# fabfm.net
KiCad netlist of a schematic drawn in EAGLE
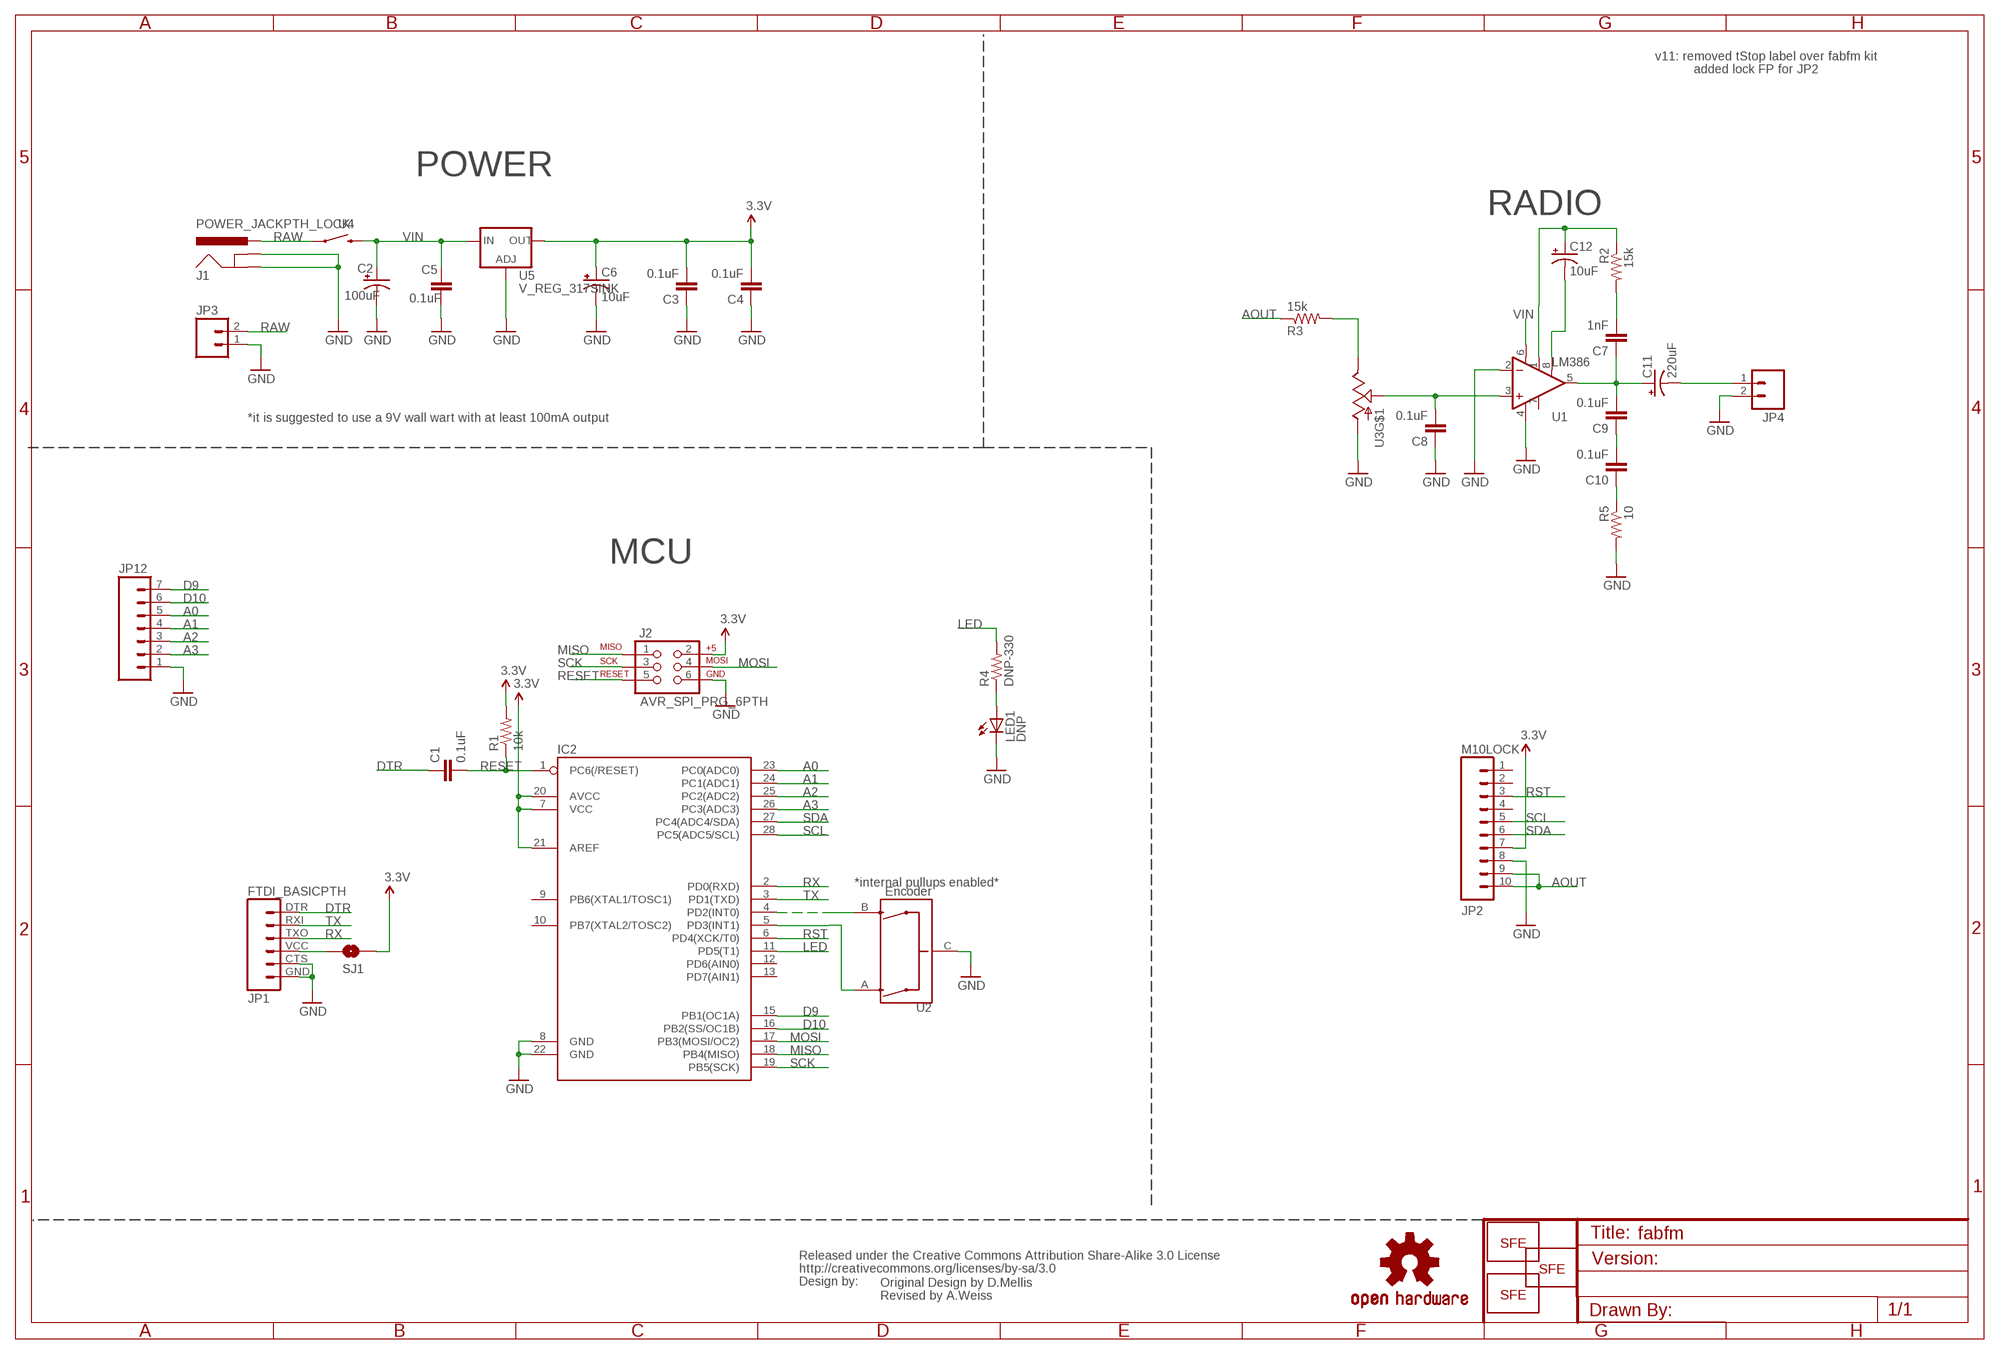
[diagram p0: schematic, sheet 1]

(export (version "E")
  (design (tool "Eeschema 10.0.6"))
  (components
    (comp (ref "C1")
      (value "0.1uF")
      (footprint "eagle-import:CAP-PTH-SMALL-KIT")
      (libsource (lib "eagle-import") (part "CAPKIT"))
    )
    (comp (ref "C2")
      (value "100uF")
      (footprint "eagle-import:CPOL-RADIAL-100UF-25V")
      (libsource (lib "eagle-import") (part "CAP_POLPTH1"))
    )
    (comp (ref "C3")
      (value "0.1uF")
      (footprint "eagle-import:CAP-PTH-SMALL-KIT")
      (libsource (lib "eagle-import") (part "CAPKIT"))
    )
    (comp (ref "C4")
      (value "0.1uF")
      (footprint "eagle-import:CAP-PTH-SMALL-KIT")
      (libsource (lib "eagle-import") (part "CAPKIT"))
    )
    (comp (ref "C5")
      (value "0.1uF")
      (footprint "eagle-import:CAP-PTH-SMALL-KIT")
      (libsource (lib "eagle-import") (part "CAPKIT"))
    )
    (comp (ref "C6")
      (value "10uF")
      (footprint "eagle-import:CPOL-RADIAL-10UF-25V")
      (libsource (lib "eagle-import") (part "CAP_POLPTH2"))
    )
    (comp (ref "C7")
      (value "1nF")
      (footprint "eagle-import:CAP-PTH-SMALL-KIT")
      (libsource (lib "eagle-import") (part "CAPKIT"))
    )
    (comp (ref "C8")
      (value "0.1uF")
      (footprint "eagle-import:CAP-PTH-SMALL-KIT")
      (libsource (lib "eagle-import") (part "CAPKIT"))
    )
    (comp (ref "C9")
      (value "0.1uF")
      (footprint "eagle-import:CAP-PTH-SMALL-KIT")
      (libsource (lib "eagle-import") (part "CAPKIT"))
    )
    (comp (ref "C10")
      (value "0.1uF")
      (footprint "eagle-import:CAP-PTH-SMALL-KIT")
      (libsource (lib "eagle-import") (part "CAPKIT"))
    )
    (comp (ref "C11")
      (value "220uF")
      (footprint "eagle-import:CPOL-RADIAL-100UF-25V")
      (libsource (lib "eagle-import") (part "CAP_POLPTH1"))
    )
    (comp (ref "C12")
      (value "10uF")
      (footprint "eagle-import:CPOL-RADIAL-10UF-25V")
      (libsource (lib "eagle-import") (part "CAP_POLPTH2"))
    )
    (comp (ref "IC2")
      (value "ATMEGA328P_PDIP_EZ_PB0")
      (footprint "eagle-import:DIL28-EZ-PB0")
      (libsource (lib "eagle-import") (part "ATMEGA328P_PDIP_EZ_PB0"))
    )
    (comp (ref "J1")
      (value "POWER_JACKPTH_LOCK")
      (footprint "eagle-import:POWER_JACK_PTH_LOCK")
      (libsource (lib "eagle-import") (part "POWER_JACKPTH_LOCK"))
    )
    (comp (ref "J2")
      (value "AVR_SPI_PRG_6PTH")
      (footprint "eagle-import:2X3")
      (libsource (lib "eagle-import") (part "AVR_SPI_PRG_6PTH"))
    )
    (comp (ref "JP1")
      (value "FTDI_BASICPTH")
      (footprint "eagle-import:FTDI_BASIC")
      (libsource (lib "eagle-import") (part "FTDI_BASICPTH"))
    )
    (comp (ref "JP2")
      (value "M10LOCK")
      (footprint "eagle-import:1X10_LOCK")
      (libsource (lib "eagle-import") (part "M10LOCK"))
    )
    (comp (ref "JP3")
      (value "M02PTH")
      (footprint "eagle-import:1X02")
      (libsource (lib "eagle-import") (part "M02PTH"))
    )
    (comp (ref "JP4")
      (value "M02PTH4")
      (footprint "eagle-import:1X02_XTRA_BIG")
      (libsource (lib "eagle-import") (part "M02PTH4"))
    )
    (comp (ref "JP8")
      (value "LOGO-SFESK")
      (footprint "eagle-import:SFE-LOGO-FLAME")
      (libsource (lib "eagle-import") (part "LOGO-SFESK"))
    )
    (comp (ref "JP9")
      (value "LOGO-SFENEW")
      (footprint "eagle-import:SFE-NEW-WEBLOGO")
      (libsource (lib "eagle-import") (part "LOGO-SFENEW"))
    )
    (comp (ref "JP11")
      (value "LOGO-SFENEW")
      (footprint "eagle-import:SFE-NEW-WEBLOGO")
      (libsource (lib "eagle-import") (part "LOGO-SFENEW"))
    )
    (comp (ref "JP12")
      (value "M07")
      (footprint "eagle-import:1X07")
      (libsource (lib "eagle-import") (part "M07"))
    )
    (comp (ref "LED1")
      (value "DNP")
      (footprint "eagle-import:LED3MM")
      (libsource (lib "eagle-import") (part "LED3MM"))
    )
    (comp (ref "R1")
      (value "10k")
      (footprint "eagle-import:AXIAL-0.4")
      (libsource (lib "eagle-import") (part "RESISTORPTH-1/4W"))
    )
    (comp (ref "R2")
      (value "15k")
      (footprint "eagle-import:AXIAL-0.4")
      (libsource (lib "eagle-import") (part "RESISTORPTH-1/4W"))
    )
    (comp (ref "R3")
      (value "15k")
      (footprint "eagle-import:AXIAL-0.4")
      (libsource (lib "eagle-import") (part "RESISTORPTH-1/4W"))
    )
    (comp (ref "R4")
      (value "DNP-330")
      (footprint "eagle-import:AXIAL-0.4")
      (libsource (lib "eagle-import") (part "RESISTORPTH-1/4W"))
    )
    (comp (ref "R5")
      (value "10")
      (footprint "eagle-import:AXIAL-0.4")
      (libsource (lib "eagle-import") (part "RESISTORPTH-1/4W"))
    )
    (comp (ref "SJ1")
      (value "SOLDERJUMPERNO")
      (footprint "eagle-import:SJ_2S-NO")
      (libsource (lib "eagle-import") (part "SOLDERJUMPERNO"))
    )
    (comp (ref "U$1")
      (value "OSHW-LOGOS")
      (footprint "eagle-import:OSHW-LOGO-S")
      (libsource (lib "eagle-import") (part "OSHW-LOGOS"))
    )
    (comp (ref "U$2")
      (value "CREATIVE_COMMONS")
      (footprint "eagle-import:CREATIVE_COMMONS")
      (libsource (lib "eagle-import") (part "CREATIVE_COMMONS"))
    )
    (comp (ref "U1")
      (value "LM386")
      (footprint "eagle-import:DIP08")
      (libsource (lib "eagle-import") (part "LM386"))
    )
    (comp (ref "U2")
      (value "Encoder")
      (footprint "eagle-import:ENCODER-16MM-QUAD")
      (libsource (lib "eagle-import") (part "ENCODER-QUADRATURE"))
    )
    (comp (ref "U3")
      (value "POT_SWITCHPOT_PTH_SWITCH")
      (footprint "eagle-import:POT_PTH_SWITCH")
      (libsource (lib "eagle-import") (part "POT_SWITCHPOT_PTH_SWITCH"))
    )
    (comp (ref "U5")
      (value "V_REG_317SINK")
      (footprint "eagle-import:TO220-ADJ")
      (libsource (lib "eagle-import") (part "V_REG_317SINK"))
    )
  )
  (nets
    (net (code "1") (name "/A0") (class "Default")
      (node (ref "IC2") (pin "23") (pinfunction "PC0(ADC0)_23") (pintype "bidirectional"))
      (node (ref "JP12") (pin "5") (pinfunction "5_5") (pintype "passive"))
    )
    (net (code "2") (name "/A1") (class "Default")
      (node (ref "IC2") (pin "24") (pinfunction "PC1(ADC1)_24") (pintype "bidirectional"))
      (node (ref "JP12") (pin "4") (pinfunction "4_4") (pintype "passive"))
    )
    (net (code "3") (name "/A2") (class "Default")
      (node (ref "IC2") (pin "25") (pinfunction "PC2(ADC2)_25") (pintype "bidirectional"))
      (node (ref "JP12") (pin "3") (pinfunction "3_3") (pintype "passive"))
    )
    (net (code "4") (name "/A3") (class "Default")
      (node (ref "IC2") (pin "26") (pinfunction "PC3(ADC3)_26") (pintype "bidirectional"))
      (node (ref "JP12") (pin "2") (pinfunction "2_2") (pintype "passive"))
    )
    (net (code "5") (name "/AOUT") (class "Default")
      (node (ref "JP2") (pin "10") (pinfunction "10_10") (pintype "passive"))
      (node (ref "JP2") (pin "9") (pinfunction "9_9") (pintype "passive"))
      (node (ref "R3") (pin "P$1") (pinfunction "1_P$1") (pintype "passive"))
    )
    (net (code "6") (name "/D9") (class "Default")
      (node (ref "IC2") (pin "15") (pinfunction "PB1(OC1A)_15") (pintype "bidirectional"))
      (node (ref "JP12") (pin "7") (pinfunction "7_7") (pintype "passive"))
    )
    (net (code "7") (name "/D10") (class "Default")
      (node (ref "IC2") (pin "16") (pinfunction "PB2(SS/OC1B)_16") (pintype "bidirectional"))
      (node (ref "JP12") (pin "6") (pinfunction "6_6") (pintype "passive"))
    )
    (net (code "8") (name "/DTR") (class "Default")
      (node (ref "C1") (pin "1") (pinfunction "1_1") (pintype "passive"))
      (node (ref "JP1") (pin "DTR") (pinfunction "1_DTR") (pintype "passive"))
    )
    (net (code "9") (name "/LED") (class "Default")
      (node (ref "IC2") (pin "11") (pinfunction "PD5(T1)_11") (pintype "bidirectional"))
      (node (ref "R4") (pin "P$2") (pinfunction "2_P$2") (pintype "passive"))
    )
    (net (code "10") (name "/MISO") (class "Default")
      (node (ref "IC2") (pin "18") (pinfunction "PB4(MISO)_18") (pintype "bidirectional"))
      (node (ref "J2") (pin "1") (pinfunction "1_1") (pintype "passive"))
    )
    (net (code "11") (name "/MOSI") (class "Default")
      (node (ref "IC2") (pin "17") (pinfunction "PB3(MOSI/OC2)_17") (pintype "bidirectional"))
      (node (ref "J2") (pin "4") (pinfunction "4_4") (pintype "passive"))
    )
    (net (code "12") (name "/RAW") (class "Default")
      (node (ref "J1") (pin "PWR") (pinfunction "PWR_PWR") (pintype "bidirectional"))
      (node (ref "JP3") (pin "2") (pinfunction "2_2") (pintype "passive"))
      (node (ref "U3") (pin "S1") (pinfunction "1_S1") (pintype "passive"))
    )
    (net (code "13") (name "/RESET") (class "Default")
      (node (ref "C1") (pin "2") (pinfunction "2_2") (pintype "passive"))
      (node (ref "IC2") (pin "1") (pinfunction "PC6(/RESET)_1") (pintype "bidirectional"))
      (node (ref "J2") (pin "5") (pinfunction "5_5") (pintype "passive"))
      (node (ref "R1") (pin "P$1") (pinfunction "1_P$1") (pintype "passive"))
    )
    (net (code "14") (name "/RST") (class "Default")
      (node (ref "IC2") (pin "6") (pinfunction "PD4(XCK/T0)_6") (pintype "bidirectional"))
      (node (ref "JP2") (pin "3") (pinfunction "3_3") (pintype "passive"))
    )
    (net (code "15") (name "/RX") (class "Default")
      (node (ref "IC2") (pin "2") (pinfunction "PD0(RXD)_2") (pintype "bidirectional"))
      (node (ref "JP1") (pin "TXO") (pinfunction "3_TXO") (pintype "passive"))
    )
    (net (code "16") (name "/SCK") (class "Default")
      (node (ref "IC2") (pin "19") (pinfunction "PB5(SCK)_19") (pintype "bidirectional"))
      (node (ref "J2") (pin "3") (pinfunction "3_3") (pintype "passive"))
    )
    (net (code "17") (name "/SCL") (class "Default")
      (node (ref "IC2") (pin "28") (pinfunction "PC5(ADC5/SCL)_28") (pintype "bidirectional"))
      (node (ref "JP2") (pin "5") (pinfunction "5_5") (pintype "passive"))
    )
    (net (code "18") (name "/SDA") (class "Default")
      (node (ref "IC2") (pin "27") (pinfunction "PC4(ADC4/SDA)_27") (pintype "bidirectional"))
      (node (ref "JP2") (pin "6") (pinfunction "6_6") (pintype "passive"))
    )
    (net (code "19") (name "/TX") (class "Default")
      (node (ref "IC2") (pin "3") (pinfunction "PD1(TXD)_3") (pintype "bidirectional"))
      (node (ref "JP1") (pin "RXI") (pinfunction "2_RXI") (pintype "passive"))
    )
    (net (code "20") (name "/VIN") (class "Default")
      (node (ref "C2") (pin "1") (pinfunction "+_1") (pintype "passive"))
      (node (ref "C5") (pin "2") (pinfunction "2_2") (pintype "passive"))
      (node (ref "U1") (pin "6") (pinfunction "V+_6") (pintype "power_in"))
      (node (ref "U3") (pin "S2") (pinfunction "2_S2") (pintype "passive"))
      (node (ref "U5") (pin "IN") (pinfunction "IN_IN") (pintype "input"))
    )
    (net (code "21") (name "3.3V") (class "Default")
      (node (ref "C3") (pin "2") (pinfunction "2_2") (pintype "passive"))
      (node (ref "C4") (pin "2") (pinfunction "2_2") (pintype "passive"))
      (node (ref "C6") (pin "1") (pinfunction "+_1") (pintype "passive"))
      (node (ref "IC2") (pin "20") (pinfunction "AVCC_20") (pintype "bidirectional"))
      (node (ref "IC2") (pin "21") (pinfunction "AREF_21") (pintype "bidirectional"))
      (node (ref "IC2") (pin "7") (pinfunction "VCC_7") (pintype "bidirectional"))
      (node (ref "J2") (pin "2") (pinfunction "2_2") (pintype "passive"))
      (node (ref "JP2") (pin "7") (pinfunction "7_7") (pintype "passive"))
      (node (ref "R1") (pin "P$2") (pinfunction "2_P$2") (pintype "passive"))
      (node (ref "SJ1") (pin "1") (pinfunction "1_1") (pintype "passive"))
      (node (ref "U5") (pin "OUT") (pinfunction "OUT_OUT") (pintype "output"))
    )
    (net (code "22") (name "GND") (class "Default")
      (node (ref "C2") (pin "2") (pinfunction "-_2") (pintype "passive"))
      (node (ref "C3") (pin "1") (pinfunction "1_1") (pintype "passive"))
      (node (ref "C4") (pin "1") (pinfunction "1_1") (pintype "passive"))
      (node (ref "C5") (pin "1") (pinfunction "1_1") (pintype "passive"))
      (node (ref "C6") (pin "2") (pinfunction "-_2") (pintype "passive"))
      (node (ref "C8") (pin "1") (pinfunction "1_1") (pintype "passive"))
      (node (ref "IC2") (pin "22") (pinfunction "GND_22") (pintype "bidirectional"))
      (node (ref "IC2") (pin "8") (pinfunction "GND_8") (pintype "bidirectional"))
      (node (ref "J1") (pin "GND") (pinfunction "GND_GND") (pintype "bidirectional"))
      (node (ref "J1") (pin "GNDBREAK") (pinfunction "GNDBREAK_GNDBREAK") (pintype "bidirectional"))
      (node (ref "J2") (pin "6") (pinfunction "6_6") (pintype "passive"))
      (node (ref "JP1") (pin "CTS") (pinfunction "5_CTS") (pintype "passive"))
      (node (ref "JP1") (pin "GND") (pinfunction "6_GND") (pintype "passive"))
      (node (ref "JP12") (pin "1") (pinfunction "1_1") (pintype "passive"))
      (node (ref "JP2") (pin "8") (pinfunction "8_8") (pintype "passive"))
      (node (ref "JP3") (pin "1") (pinfunction "1_1") (pintype "passive"))
      (node (ref "JP4") (pin "2") (pinfunction "2_2") (pintype "passive"))
      (node (ref "LED1") (pin "K") (pinfunction "C_K") (pintype "passive"))
      (node (ref "R5") (pin "P$2") (pinfunction "2_P$2") (pintype "passive"))
      (node (ref "U1") (pin "2") (pinfunction "-IN_2") (pintype "input"))
      (node (ref "U1") (pin "4") (pinfunction "V-_4") (pintype "power_in"))
      (node (ref "U2") (pin "C") (pinfunction "C_C") (pintype "bidirectional"))
      (node (ref "U3") (pin "1") (pinfunction "A_1") (pintype "passive"))
      (node (ref "U5") (pin "ADJ") (pinfunction "ADJ_ADJ") (pintype "input"))
    )
    (net (code "23") (name "Net-(C10-Pad2)") (class "Default")
      (node (ref "C10") (pin "2") (pinfunction "2_2") (pintype "passive"))
      (node (ref "C9") (pin "1") (pinfunction "1_1") (pintype "passive"))
    )
    (net (code "24") (name "Net-(C11-+)") (class "Default")
      (node (ref "C11") (pin "1") (pinfunction "+_1") (pintype "passive"))
      (node (ref "C7") (pin "1") (pinfunction "1_1") (pintype "passive"))
      (node (ref "C9") (pin "2") (pinfunction "2_2") (pintype "passive"))
      (node (ref "U1") (pin "5") (pinfunction "OUT_5") (pintype "output"))
    )
    (net (code "25") (name "Net-(C11--)") (class "Default")
      (node (ref "C11") (pin "2") (pinfunction "-_2") (pintype "passive"))
      (node (ref "JP4") (pin "1") (pinfunction "1_1") (pintype "passive"))
    )
    (net (code "26") (name "Net-(C12-+)") (class "Default")
      (node (ref "C12") (pin "1") (pinfunction "+_1") (pintype "passive"))
      (node (ref "R2") (pin "P$1") (pinfunction "1_P$1") (pintype "passive"))
      (node (ref "U1") (pin "1") (pinfunction "GAIN_1") (pintype "bidirectional"))
    )
    (net (code "27") (name "Net-(C12--)") (class "Default")
      (node (ref "C12") (pin "2") (pinfunction "-_2") (pintype "passive"))
      (node (ref "U1") (pin "8") (pinfunction "GAIN_8") (pintype "bidirectional"))
    )
    (net (code "28") (name "Net-(IC2-PD2(INT0))") (class "Default")
      (node (ref "IC2") (pin "4") (pinfunction "PD2(INT0)_4") (pintype "bidirectional"))
      (node (ref "U2") (pin "B") (pinfunction "B_B") (pintype "bidirectional"))
    )
    (net (code "29") (name "Net-(IC2-PD3(INT1))") (class "Default")
      (node (ref "IC2") (pin "5") (pinfunction "PD3(INT1)_5") (pintype "bidirectional"))
      (node (ref "U2") (pin "A") (pinfunction "A_A") (pintype "bidirectional"))
    )
    (net (code "30") (name "Net-(JP1-4)") (class "Default")
      (node (ref "JP1") (pin "VCC") (pinfunction "4_VCC") (pintype "passive"))
      (node (ref "SJ1") (pin "2") (pinfunction "2_2") (pintype "passive"))
    )
    (net (code "31") (name "Net-(R2-2)") (class "Default")
      (node (ref "C7") (pin "2") (pinfunction "2_2") (pintype "passive"))
      (node (ref "R2") (pin "P$2") (pinfunction "2_P$2") (pintype "passive"))
    )
    (net (code "32") (name "Net-(R3-2)") (class "Default")
      (node (ref "R3") (pin "P$2") (pinfunction "2_P$2") (pintype "passive"))
      (node (ref "U3") (pin "3") (pinfunction "E_3") (pintype "passive"))
    )
    (net (code "33") (name "Net-(R4-1)") (class "Default")
      (node (ref "LED1") (pin "A") (pinfunction "A_A") (pintype "passive"))
      (node (ref "R4") (pin "P$1") (pinfunction "1_P$1") (pintype "passive"))
    )
    (net (code "34") (name "Net-(R5-1)") (class "Default")
      (node (ref "C10") (pin "1") (pinfunction "1_1") (pintype "passive"))
      (node (ref "R5") (pin "P$1") (pinfunction "1_P$1") (pintype "passive"))
    )
    (net (code "35") (name "Net-(U1-+IN)") (class "Default")
      (node (ref "C8") (pin "2") (pinfunction "2_2") (pintype "passive"))
      (node (ref "U1") (pin "3") (pinfunction "+IN_3") (pintype "input"))
      (node (ref "U3") (pin "2") (pinfunction "S_2") (pintype "passive"))
    )
    (net (code "36") (name "unconnected-(IC2-PB6(XTAL1{slash}TOSC1)-Pad9)") (class "Default")
      (node (ref "IC2") (pin "9") (pinfunction "PB6(XTAL1/TOSC1)_9") (pintype "bidirectional"))
    )
    (net (code "37") (name "unconnected-(IC2-PB7(XTAL2{slash}TOSC2)-Pad10)") (class "Default")
      (node (ref "IC2") (pin "10") (pinfunction "PB7(XTAL2/TOSC2)_10") (pintype "bidirectional"))
    )
    (net (code "38") (name "unconnected-(IC2-PD6(AIN0)-Pad12)") (class "Default")
      (node (ref "IC2") (pin "12") (pinfunction "PD6(AIN0)_12") (pintype "bidirectional"))
    )
    (net (code "39") (name "unconnected-(IC2-PD7(AIN1)-Pad13)") (class "Default")
      (node (ref "IC2") (pin "13") (pinfunction "PD7(AIN1)_13") (pintype "bidirectional"))
    )
    (net (code "40") (name "unconnected-(JP2-Pad1)") (class "Default")
      (node (ref "JP2") (pin "1") (pinfunction "1_1") (pintype "passive"))
    )
    (net (code "41") (name "unconnected-(JP2-Pad2)") (class "Default")
      (node (ref "JP2") (pin "2") (pinfunction "2_2") (pintype "passive"))
    )
    (net (code "42") (name "unconnected-(JP2-Pad4)") (class "Default")
      (node (ref "JP2") (pin "4") (pinfunction "4_4") (pintype "passive"))
    )
    (net (code "43") (name "unconnected-(U1-BP-Pad7)") (class "Default")
      (node (ref "U1") (pin "7") (pinfunction "BP_7") (pintype "bidirectional"))
    )
  )
)
